# tea_maker_without_autorouter.net
KiCad netlist of a schematic drawn in EAGLE
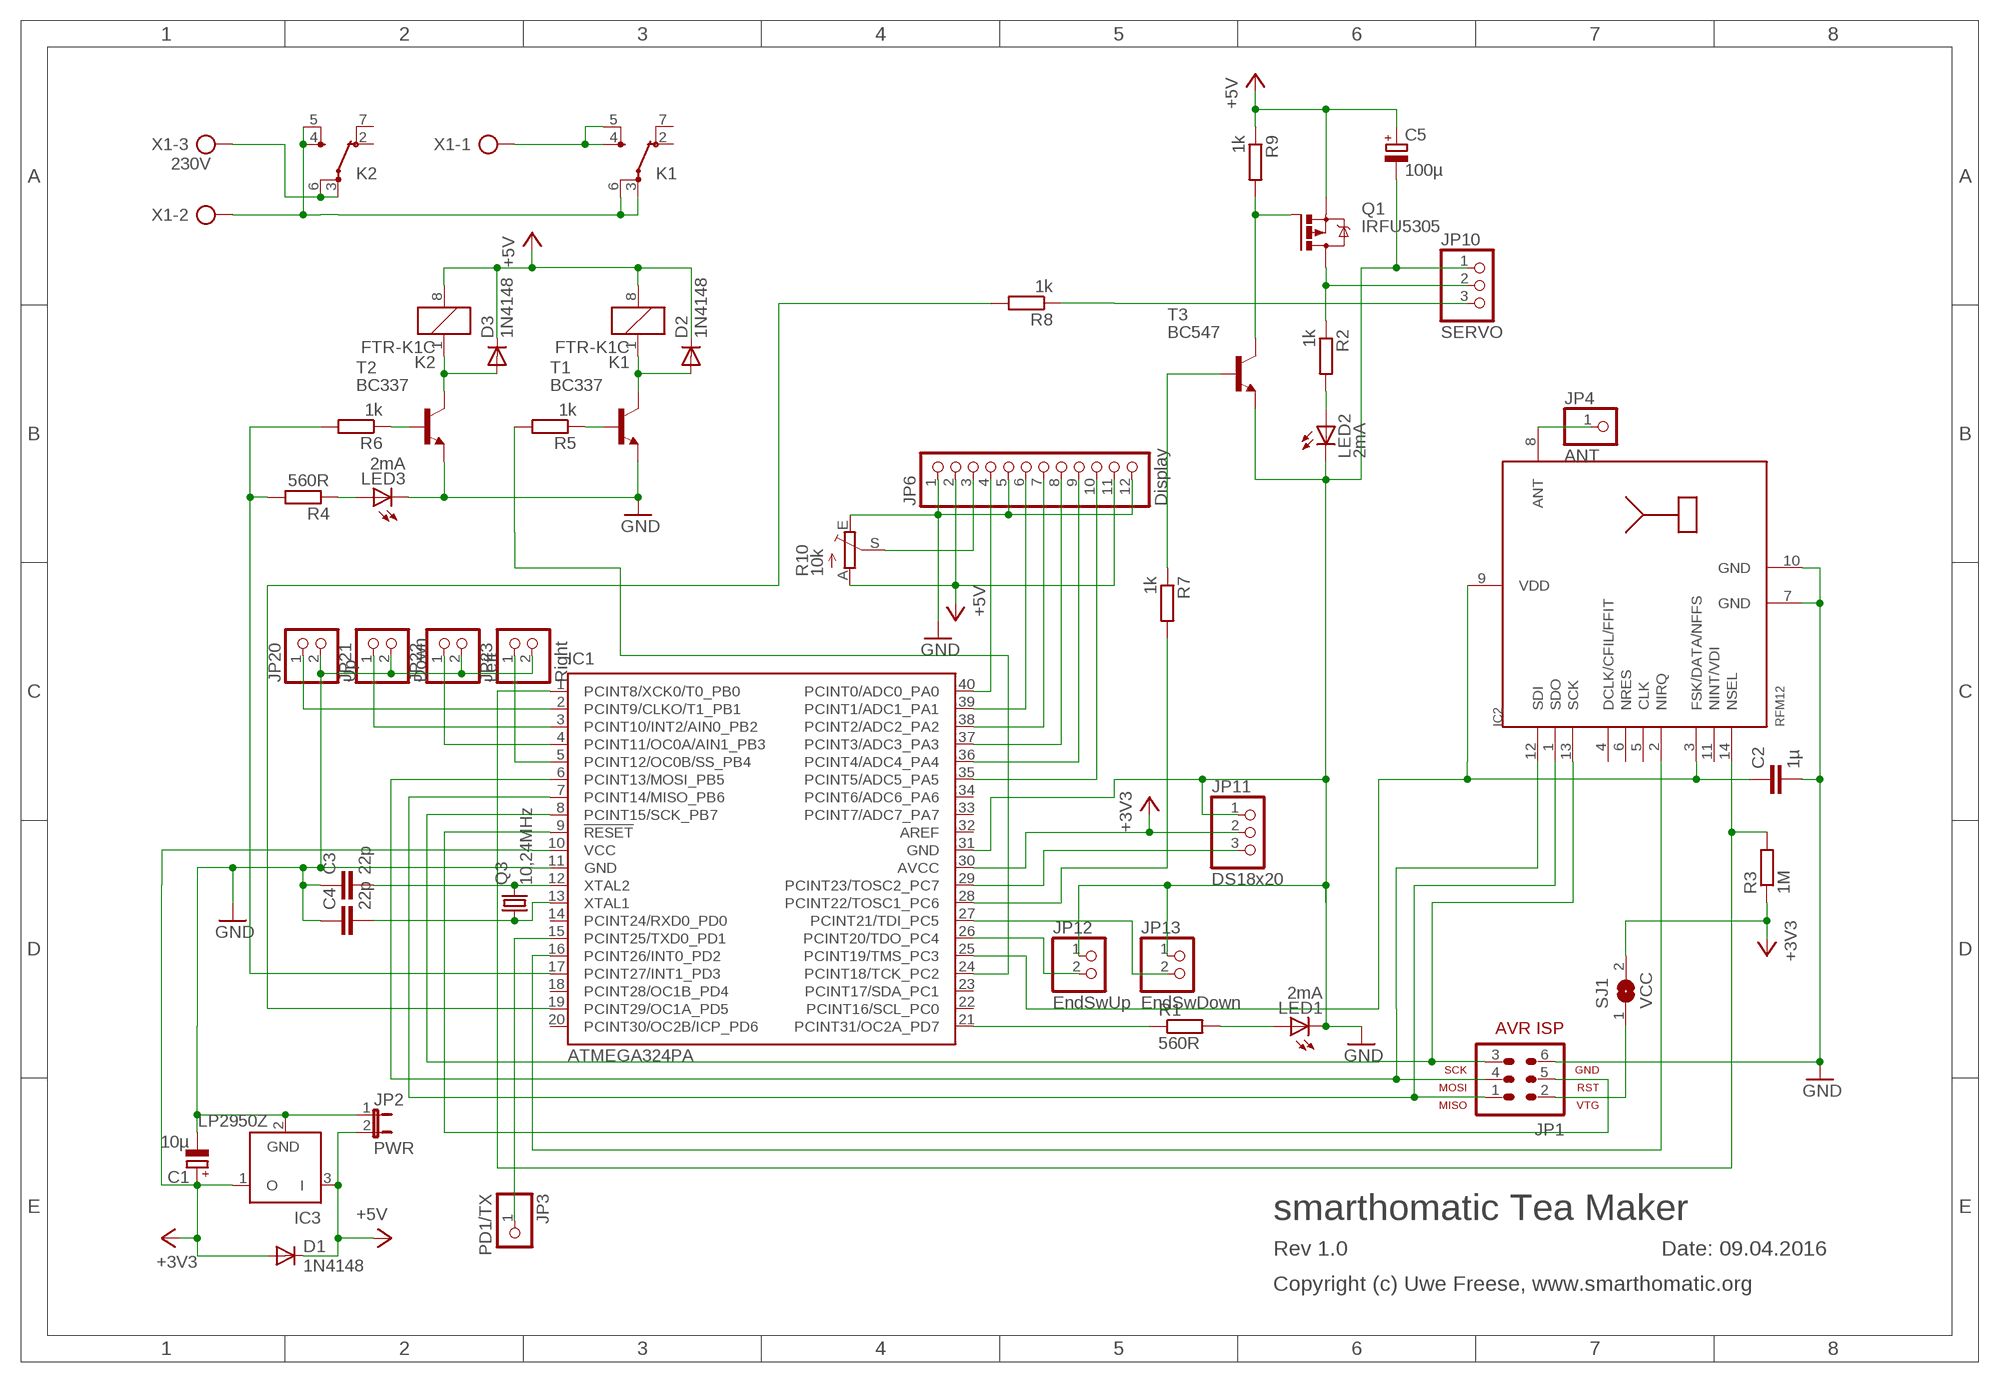
[diagram p0: schematic, sheet 1]

(export (version "E")
  (design (tool "Eeschema 10.0.6"))
  (components
    (comp (ref "C1")
      (value "10µ")
      (footprint "eagle-import:E1,8-4")
      (libsource (lib "eagle-import") (part "CPOL-EUE1.8-4"))
    )
    (comp (ref "C2")
      (value "1µ")
      (footprint "eagle-import:C5B3.5")
      (libsource (lib "eagle-import") (part "C5/3.5"))
    )
    (comp (ref "C3")
      (value "22p")
      (footprint "eagle-import:C025-024X044")
      (libsource (lib "eagle-import") (part "C-EU025-024X044"))
    )
    (comp (ref "C4")
      (value "22p")
      (footprint "eagle-import:C025-024X044")
      (libsource (lib "eagle-import") (part "C-EU025-024X044"))
    )
    (comp (ref "C5")
      (value "100µ")
      (footprint "eagle-import:E2,5-7")
      (libsource (lib "eagle-import") (part "CPOL-EUE2.5-7"))
    )
    (comp (ref "D1")
      (value "1N4148")
      (footprint "eagle-import:DO35-7")
      (libsource (lib "eagle-import") (part "1N4148DO35-7"))
    )
    (comp (ref "D2")
      (value "1N4148")
      (footprint "eagle-import:DO35-7")
      (libsource (lib "eagle-import") (part "1N4148DO35-7"))
    )
    (comp (ref "D3")
      (value "1N4148")
      (footprint "eagle-import:DO35-7")
      (libsource (lib "eagle-import") (part "1N4148DO35-7"))
    )
    (comp (ref "IC1")
      (value "ATMEGA324PA")
      (footprint "eagle-import:DIL40")
      (fields (field (name "MPN") "ATMEGA644V-10PU"))
      (libsource (lib "eagle-import") (part "ATMEGA644-PU10"))
    )
    (comp (ref "IC2")
      (value "RFM12")
      (footprint "eagle-import:RFM")
      (libsource (lib "eagle-import") (part "RFM12"))
    )
    (comp (ref "IC3")
      (value "LP2950Z")
      (footprint "eagle-import:TO92")
      (libsource (lib "eagle-import") (part "LP2950Z"))
    )
    (comp (ref "JP1")
      (value "AVR-ISP-6")
      (footprint "eagle-import:AVR-ISP-6")
      (libsource (lib "eagle-import") (part "AVR-ISP-6"))
    )
    (comp (ref "JP2")
      (value "PWR")
      (footprint "eagle-import:JP1")
      (libsource (lib "eagle-import") (part "JP1E"))
    )
    (comp (ref "JP3")
      (value "PD1/TX")
      (footprint "eagle-import:1X01")
      (libsource (lib "eagle-import") (part "PINHD-1X1"))
    )
    (comp (ref "JP4")
      (value "ANT")
      (footprint "eagle-import:1X01")
      (libsource (lib "eagle-import") (part "PINHD-1X1"))
    )
    (comp (ref "JP6")
      (value "Display")
      (footprint "eagle-import:1X12")
      (libsource (lib "eagle-import") (part "PINHD-1X12"))
    )
    (comp (ref "JP10")
      (value "SERVO")
      (footprint "eagle-import:1X03")
      (libsource (lib "eagle-import") (part "PINHD-1X3"))
    )
    (comp (ref "JP11")
      (value "DS18x20")
      (footprint "eagle-import:1X03")
      (libsource (lib "eagle-import") (part "PINHD-1X3"))
    )
    (comp (ref "JP12")
      (value "EndSwUp")
      (footprint "eagle-import:1X02")
      (libsource (lib "eagle-import") (part "PINHD-1X2"))
    )
    (comp (ref "JP13")
      (value "EndSwDown")
      (footprint "eagle-import:1X02")
      (libsource (lib "eagle-import") (part "PINHD-1X2"))
    )
    (comp (ref "JP20")
      (value "Up")
      (footprint "eagle-import:1X02")
      (libsource (lib "eagle-import") (part "PINHD-1X2"))
    )
    (comp (ref "JP21")
      (value "Down")
      (footprint "eagle-import:1X02")
      (libsource (lib "eagle-import") (part "PINHD-1X2"))
    )
    (comp (ref "JP22")
      (value "Left")
      (footprint "eagle-import:1X02")
      (libsource (lib "eagle-import") (part "PINHD-1X2"))
    )
    (comp (ref "JP23")
      (value "Right")
      (footprint "eagle-import:1X02")
      (libsource (lib "eagle-import") (part "PINHD-1X2"))
    )
    (comp (ref "K1")
      (value "FTR-K1C")
      (footprint "eagle-import:FTR-K1C")
      (libsource (lib "eagle-import") (part "FTR-K1C"))
    )
    (comp (ref "K2")
      (value "FTR-K1C")
      (footprint "eagle-import:FTR-K1C")
      (libsource (lib "eagle-import") (part "FTR-K1C"))
    )
    (comp (ref "LED1")
      (value "2mA")
      (footprint "eagle-import:LED3MM")
      (libsource (lib "eagle-import") (part "LED3MM"))
    )
    (comp (ref "LED2")
      (value "2mA")
      (footprint "eagle-import:LED3MM")
      (libsource (lib "eagle-import") (part "LED3MM"))
    )
    (comp (ref "LED3")
      (value "2mA")
      (footprint "eagle-import:LED3MM")
      (libsource (lib "eagle-import") (part "LED3MM"))
    )
    (comp (ref "Q1")
      (value "IRFU5305")
      (footprint "eagle-import:I-PAK_TO251AA")
      (libsource (lib "eagle-import") (part "IRF?5305U"))
    )
    (comp (ref "Q3")
      (value "10,24MHz")
      (footprint "eagle-import:HC49_S")
      (libsource (lib "eagle-import") (part "CRYSTALHC49S"))
    )
    (comp (ref "R1")
      (value "560R")
      (footprint "eagle-import:0207_7")
      (libsource (lib "eagle-import") (part "R-EU_0207/7"))
    )
    (comp (ref "R2")
      (value "1k")
      (footprint "eagle-import:0207_7")
      (libsource (lib "eagle-import") (part "R-EU_0207/7"))
    )
    (comp (ref "R3")
      (value "1M")
      (footprint "eagle-import:0207_7")
      (libsource (lib "eagle-import") (part "R-EU_0207/7"))
    )
    (comp (ref "R4")
      (value "560R")
      (footprint "eagle-import:0207_7")
      (libsource (lib "eagle-import") (part "R-EU_0207/7"))
    )
    (comp (ref "R5")
      (value "1k")
      (footprint "eagle-import:0207_7")
      (libsource (lib "eagle-import") (part "R-EU_0207/7"))
    )
    (comp (ref "R6")
      (value "1k")
      (footprint "eagle-import:0207_7")
      (libsource (lib "eagle-import") (part "R-EU_0207/7"))
    )
    (comp (ref "R7")
      (value "1k")
      (footprint "eagle-import:0207_7")
      (libsource (lib "eagle-import") (part "R-EU_0207/7"))
    )
    (comp (ref "R8")
      (value "1k")
      (footprint "eagle-import:0207_7")
      (libsource (lib "eagle-import") (part "R-EU_0207/7"))
    )
    (comp (ref "R9")
      (value "1k")
      (footprint "eagle-import:0207_7")
      (libsource (lib "eagle-import") (part "R-EU_0207/7"))
    )
    (comp (ref "R10")
      (value "10k")
      (footprint "eagle-import:PT-10S")
      (libsource (lib "eagle-import") (part "TRIM_EU-PT10S"))
    )
    (comp (ref "SJ1")
      (value "VCC")
      (footprint "eagle-import:SJ")
      (libsource (lib "eagle-import") (part "SJ"))
    )
    (comp (ref "T1")
      (value "BC337")
      (footprint "eagle-import:TO92")
      (libsource (lib "eagle-import") (part "BC337"))
    )
    (comp (ref "T2")
      (value "BC337")
      (footprint "eagle-import:TO92")
      (libsource (lib "eagle-import") (part "BC337"))
    )
    (comp (ref "T3")
      (value "BC547")
      (footprint "eagle-import:TO92")
      (libsource (lib "eagle-import") (part "BC547"))
    )
    (comp (ref "X1")
      (value "230V")
      (footprint "eagle-import:AK500_3")
      (libsource (lib "eagle-import") (part "AK500/3"))
    )
  )
  (nets
    (net (code "1") (name "+3V3") (class "Default")
      (node (ref "C1") (pin "+") (pinfunction "+_+") (pintype "passive"))
      (node (ref "D1") (pin "A") (pinfunction "A_A") (pintype "passive"))
      (node (ref "IC1") (pin "10") (pinfunction "VCC_10") (pintype "power_in"))
      (node (ref "IC1") (pin "30") (pinfunction "AVCC_30") (pintype "power_in"))
      (node (ref "IC3") (pin "1") (pinfunction "O_1") (pintype "input"))
      (node (ref "JP11") (pin "2") (pinfunction "2_2") (pintype "passive"))
      (node (ref "R3") (pin "1") (pinfunction "1_1") (pintype "passive"))
      (node (ref "SJ1") (pin "2") (pinfunction "2_2") (pintype "passive"))
    )
    (net (code "2") (name "+5V") (class "Default")
      (node (ref "C5") (pin "+") (pinfunction "+_+") (pintype "passive"))
      (node (ref "D1") (pin "C") (pinfunction "C_C") (pintype "passive"))
      (node (ref "D2") (pin "C") (pinfunction "C_C") (pintype "passive"))
      (node (ref "D3") (pin "C") (pinfunction "C_C") (pintype "passive"))
      (node (ref "IC3") (pin "3") (pinfunction "I_3") (pintype "input"))
      (node (ref "JP2") (pin "2") (pinfunction "2_2") (pintype "passive"))
      (node (ref "JP6") (pin "11") (pinfunction "11_11") (pintype "passive"))
      (node (ref "JP6") (pin "2") (pinfunction "2_2") (pintype "passive"))
      (node (ref "K1") (pin "8") (pinfunction "2_8") (pintype "passive"))
      (node (ref "K2") (pin "8") (pinfunction "2_8") (pintype "passive"))
      (node (ref "Q1") (pin "3") (pinfunction "S_3") (pintype "passive"))
      (node (ref "R10") (pin "A") (pinfunction "A_A") (pintype "passive"))
      (node (ref "R9") (pin "1") (pinfunction "1_1") (pintype "passive"))
    )
    (net (code "3") (name "GND") (class "Default")
      (node (ref "C1") (pin "-") (pinfunction "-_-") (pintype "passive"))
      (node (ref "C2") (pin "2") (pinfunction "2_2") (pintype "passive"))
      (node (ref "C3") (pin "1") (pinfunction "1_1") (pintype "passive"))
      (node (ref "C4") (pin "1") (pinfunction "1_1") (pintype "passive"))
      (node (ref "C5") (pin "-") (pinfunction "-_-") (pintype "passive"))
      (node (ref "IC1") (pin "11") (pinfunction "GND_11") (pintype "power_in"))
      (node (ref "IC1") (pin "31") (pinfunction "GND_31") (pintype "power_in"))
      (node (ref "IC2") (pin "10") (pinfunction "GND_10") (pintype "power_in"))
      (node (ref "IC2") (pin "7") (pinfunction "GND_7") (pintype "power_in"))
      (node (ref "IC3") (pin "2") (pinfunction "GND_2") (pintype "power_in"))
      (node (ref "JP1") (pin "6") (pinfunction "6_6") (pintype "passive"))
      (node (ref "JP10") (pin "1") (pinfunction "1_1") (pintype "passive"))
      (node (ref "JP11") (pin "1") (pinfunction "1_1") (pintype "passive"))
      (node (ref "JP12") (pin "1") (pinfunction "1_1") (pintype "passive"))
      (node (ref "JP13") (pin "1") (pinfunction "1_1") (pintype "passive"))
      (node (ref "JP2") (pin "1") (pinfunction "1_1") (pintype "passive"))
      (node (ref "JP20") (pin "2") (pinfunction "2_2") (pintype "passive"))
      (node (ref "JP21") (pin "2") (pinfunction "2_2") (pintype "passive"))
      (node (ref "JP22") (pin "2") (pinfunction "2_2") (pintype "passive"))
      (node (ref "JP23") (pin "2") (pinfunction "2_2") (pintype "passive"))
      (node (ref "JP6") (pin "1") (pinfunction "1_1") (pintype "passive"))
      (node (ref "JP6") (pin "12") (pinfunction "12_12") (pintype "passive"))
      (node (ref "JP6") (pin "5") (pinfunction "5_5") (pintype "passive"))
      (node (ref "LED1") (pin "K") (pinfunction "C_K") (pintype "passive"))
      (node (ref "LED2") (pin "K") (pinfunction "C_K") (pintype "passive"))
      (node (ref "LED3") (pin "K") (pinfunction "C_K") (pintype "passive"))
      (node (ref "R10") (pin "E") (pinfunction "E_E") (pintype "passive"))
      (node (ref "T1") (pin "1") (pinfunction "E_1") (pintype "passive"))
      (node (ref "T2") (pin "1") (pinfunction "E_1") (pintype "passive"))
      (node (ref "T3") (pin "1") (pinfunction "E_1") (pintype "passive"))
    )
    (net (code "4") (name "Net-(IC1-PCINT0{slash}ADC0_PA0)") (class "Default")
      (node (ref "IC1") (pin "40") (pinfunction "PCINT0/ADC0_PA0_40") (pintype "bidirectional"))
      (node (ref "JP6") (pin "4") (pinfunction "4_4") (pintype "passive"))
    )
    (net (code "5") (name "Net-(IC1-PCINT1{slash}ADC1_PA1)") (class "Default")
      (node (ref "IC1") (pin "39") (pinfunction "PCINT1/ADC1_PA1_39") (pintype "bidirectional"))
      (node (ref "JP6") (pin "6") (pinfunction "6_6") (pintype "passive"))
    )
    (net (code "6") (name "Net-(IC1-PCINT2{slash}ADC2_PA2)") (class "Default")
      (node (ref "IC1") (pin "38") (pinfunction "PCINT2/ADC2_PA2_38") (pintype "bidirectional"))
      (node (ref "JP6") (pin "7") (pinfunction "7_7") (pintype "passive"))
    )
    (net (code "7") (name "Net-(IC1-PCINT3{slash}ADC3_PA3)") (class "Default")
      (node (ref "IC1") (pin "37") (pinfunction "PCINT3/ADC3_PA3_37") (pintype "bidirectional"))
      (node (ref "JP6") (pin "8") (pinfunction "8_8") (pintype "passive"))
    )
    (net (code "8") (name "Net-(IC1-PCINT4{slash}ADC4_PA4)") (class "Default")
      (node (ref "IC1") (pin "36") (pinfunction "PCINT4/ADC4_PA4_36") (pintype "bidirectional"))
      (node (ref "JP6") (pin "9") (pinfunction "9_9") (pintype "passive"))
    )
    (net (code "9") (name "Net-(IC1-PCINT5{slash}ADC5_PA5)") (class "Default")
      (node (ref "IC1") (pin "35") (pinfunction "PCINT5/ADC5_PA5_35") (pintype "bidirectional"))
      (node (ref "JP6") (pin "10") (pinfunction "10_10") (pintype "passive"))
    )
    (net (code "10") (name "Net-(IC1-PCINT8{slash}XCK0{slash}T0_PB0)") (class "Default")
      (node (ref "IC1") (pin "1") (pinfunction "PCINT8/XCK0/T0_PB0_1") (pintype "bidirectional"))
      (node (ref "IC2") (pin "14") (pinfunction "NSEL_14") (pintype "bidirectional"))
      (node (ref "R3") (pin "2") (pinfunction "2_2") (pintype "passive"))
    )
    (net (code "11") (name "Net-(IC1-PCINT9{slash}CLKO{slash}T1_PB1)") (class "Default")
      (node (ref "IC1") (pin "2") (pinfunction "PCINT9/CLKO/T1_PB1_2") (pintype "bidirectional"))
      (node (ref "JP20") (pin "1") (pinfunction "1_1") (pintype "passive"))
    )
    (net (code "12") (name "Net-(IC1-PCINT10{slash}INT2{slash}AIN0_PB2)") (class "Default")
      (node (ref "IC1") (pin "3") (pinfunction "PCINT10/INT2/AIN0_PB2_3") (pintype "bidirectional"))
      (node (ref "JP21") (pin "1") (pinfunction "1_1") (pintype "passive"))
    )
    (net (code "13") (name "Net-(IC1-PCINT11{slash}OC0A{slash}AIN1_PB3)") (class "Default")
      (node (ref "IC1") (pin "4") (pinfunction "PCINT11/OC0A/AIN1_PB3_4") (pintype "bidirectional"))
      (node (ref "JP22") (pin "1") (pinfunction "1_1") (pintype "passive"))
    )
    (net (code "14") (name "Net-(IC1-PCINT12{slash}OC0B{slash}SS_PB4)") (class "Default")
      (node (ref "IC1") (pin "5") (pinfunction "PCINT12/OC0B/SS_PB4_5") (pintype "bidirectional"))
      (node (ref "JP23") (pin "1") (pinfunction "1_1") (pintype "passive"))
    )
    (net (code "15") (name "Net-(IC1-PCINT13{slash}MOSI_PB5)") (class "Default")
      (node (ref "IC1") (pin "6") (pinfunction "PCINT13/MOSI_PB5_6") (pintype "bidirectional"))
      (node (ref "IC2") (pin "12") (pinfunction "SDI_12") (pintype "bidirectional"))
      (node (ref "JP1") (pin "4") (pinfunction "4_4") (pintype "passive"))
    )
    (net (code "16") (name "Net-(IC1-PCINT14{slash}MISO_PB6)") (class "Default")
      (node (ref "IC1") (pin "7") (pinfunction "PCINT14/MISO_PB6_7") (pintype "bidirectional"))
      (node (ref "IC2") (pin "1") (pinfunction "SDO_1") (pintype "bidirectional"))
      (node (ref "JP1") (pin "1") (pinfunction "1_1") (pintype "passive"))
    )
    (net (code "17") (name "Net-(IC1-PCINT15{slash}SCK_PB7)") (class "Default")
      (node (ref "IC1") (pin "8") (pinfunction "PCINT15/SCK_PB7_8") (pintype "bidirectional"))
      (node (ref "IC2") (pin "13") (pinfunction "SCK_13") (pintype "bidirectional"))
      (node (ref "JP1") (pin "3") (pinfunction "3_3") (pintype "passive"))
    )
    (net (code "18") (name "Net-(IC1-PCINT18{slash}TCK_PC2)") (class "Default")
      (node (ref "IC1") (pin "24") (pinfunction "PCINT18/TCK_PC2_24") (pintype "bidirectional"))
      (node (ref "R5") (pin "2") (pinfunction "2_2") (pintype "passive"))
    )
    (net (code "19") (name "Net-(IC1-PCINT19{slash}TMS_PC3)") (class "Default")
      (node (ref "C2") (pin "1") (pinfunction "1_1") (pintype "passive"))
      (node (ref "IC1") (pin "25") (pinfunction "PCINT19/TMS_PC3_25") (pintype "bidirectional"))
      (node (ref "IC2") (pin "3") (pinfunction "FSK/DATA/NFFS_3") (pintype "bidirectional"))
      (node (ref "IC2") (pin "9") (pinfunction "VDD_9") (pintype "power_in"))
    )
    (net (code "20") (name "Net-(IC1-PCINT20{slash}TDO_PC4)") (class "Default")
      (node (ref "IC1") (pin "26") (pinfunction "PCINT20/TDO_PC4_26") (pintype "bidirectional"))
      (node (ref "JP12") (pin "2") (pinfunction "2_2") (pintype "passive"))
    )
    (net (code "21") (name "Net-(IC1-PCINT21{slash}TDI_PC5)") (class "Default")
      (node (ref "IC1") (pin "27") (pinfunction "PCINT21/TDI_PC5_27") (pintype "bidirectional"))
      (node (ref "JP13") (pin "2") (pinfunction "2_2") (pintype "passive"))
    )
    (net (code "22") (name "Net-(IC1-PCINT22{slash}TOSC1_PC6)") (class "Default")
      (node (ref "IC1") (pin "28") (pinfunction "PCINT22/TOSC1_PC6_28") (pintype "bidirectional"))
      (node (ref "R7") (pin "2") (pinfunction "2_2") (pintype "passive"))
    )
    (net (code "23") (name "Net-(IC1-PCINT23{slash}TOSC2_PC7)") (class "Default")
      (node (ref "IC1") (pin "29") (pinfunction "PCINT23/TOSC2_PC7_29") (pintype "bidirectional"))
      (node (ref "JP11") (pin "3") (pinfunction "3_3") (pintype "passive"))
    )
    (net (code "24") (name "Net-(IC1-PCINT25{slash}TXD0_PD1)") (class "Default")
      (node (ref "IC1") (pin "15") (pinfunction "PCINT25/TXD0_PD1_15") (pintype "bidirectional"))
      (node (ref "JP3") (pin "1") (pinfunction "1_1") (pintype "passive"))
    )
    (net (code "25") (name "Net-(IC1-PCINT26{slash}INT0_PD2)") (class "Default")
      (node (ref "IC1") (pin "16") (pinfunction "PCINT26/INT0_PD2_16") (pintype "bidirectional"))
      (node (ref "IC2") (pin "2") (pinfunction "NIRQ_2") (pintype "bidirectional"))
    )
    (net (code "26") (name "Net-(IC1-PCINT27{slash}INT1_PD3)") (class "Default")
      (node (ref "IC1") (pin "17") (pinfunction "PCINT27/INT1_PD3_17") (pintype "bidirectional"))
      (node (ref "R4") (pin "2") (pinfunction "2_2") (pintype "passive"))
      (node (ref "R6") (pin "2") (pinfunction "2_2") (pintype "passive"))
    )
    (net (code "27") (name "Net-(IC1-PCINT29{slash}OC1A_PD5)") (class "Default")
      (node (ref "IC1") (pin "19") (pinfunction "PCINT29/OC1A_PD5_19") (pintype "bidirectional"))
      (node (ref "R8") (pin "2") (pinfunction "2_2") (pintype "passive"))
    )
    (net (code "28") (name "Net-(IC1-PCINT31{slash}OC2A_PD7)") (class "Default")
      (node (ref "IC1") (pin "21") (pinfunction "PCINT31/OC2A_PD7_21") (pintype "bidirectional"))
      (node (ref "R1") (pin "1") (pinfunction "1_1") (pintype "passive"))
    )
    (net (code "29") (name "Net-(IC1-XTAL1)") (class "Default")
      (node (ref "C4") (pin "2") (pinfunction "2_2") (pintype "passive"))
      (node (ref "IC1") (pin "13") (pinfunction "XTAL1_13") (pintype "input"))
      (node (ref "Q3") (pin "1") (pinfunction "1_1") (pintype "passive"))
    )
    (net (code "30") (name "Net-(IC1-XTAL2)") (class "Default")
      (node (ref "C3") (pin "2") (pinfunction "2_2") (pintype "passive"))
      (node (ref "IC1") (pin "12") (pinfunction "XTAL2_12") (pintype "output"))
      (node (ref "Q3") (pin "2") (pinfunction "2_2") (pintype "passive"))
    )
    (net (code "31") (name "Net-(IC1-~{RESET})") (class "Default")
      (node (ref "IC1") (pin "9") (pinfunction "~{RESET}_9") (pintype "input"))
      (node (ref "JP1") (pin "5") (pinfunction "5_5") (pintype "passive"))
    )
    (net (code "32") (name "Net-(IC2-ANT)") (class "Default")
      (node (ref "IC2") (pin "8") (pinfunction "ANT_8") (pintype "output"))
      (node (ref "JP4") (pin "1") (pinfunction "1_1") (pintype "passive"))
    )
    (net (code "33") (name "Net-(JP1-Pad2)") (class "Default")
      (node (ref "JP1") (pin "2") (pinfunction "2_2") (pintype "passive"))
      (node (ref "SJ1") (pin "1") (pinfunction "1_1") (pintype "passive"))
    )
    (net (code "34") (name "Net-(JP6-Pad3)") (class "Default")
      (node (ref "JP6") (pin "3") (pinfunction "3_3") (pintype "passive"))
      (node (ref "R10") (pin "S") (pinfunction "S_S") (pintype "passive"))
    )
    (net (code "35") (name "Net-(JP10-Pad3)") (class "Default")
      (node (ref "JP10") (pin "3") (pinfunction "3_3") (pintype "passive"))
      (node (ref "R8") (pin "1") (pinfunction "1_1") (pintype "passive"))
    )
    (net (code "36") (name "Net-(K1A-PA)") (class "Default")
      (node (ref "K1") (pin "3") (pinfunction "PA_3") (pintype "passive"))
      (node (ref "K1") (pin "6") (pinfunction "PB_6") (pintype "passive"))
      (node (ref "K2") (pin "4") (pinfunction "SA_4") (pintype "passive"))
      (node (ref "K2") (pin "5") (pinfunction "SB_5") (pintype "passive"))
      (node (ref "X1") (pin "2") (pinfunction "KL_2") (pintype "passive"))
    )
    (net (code "37") (name "Net-(K1A-SA)") (class "Default")
      (node (ref "K1") (pin "4") (pinfunction "SA_4") (pintype "passive"))
      (node (ref "K1") (pin "5") (pinfunction "SB_5") (pintype "passive"))
      (node (ref "X1") (pin "1") (pinfunction "KL_1") (pintype "passive"))
    )
    (net (code "38") (name "Net-(K2A-PA)") (class "Default")
      (node (ref "K2") (pin "3") (pinfunction "PA_3") (pintype "passive"))
      (node (ref "K2") (pin "6") (pinfunction "PB_6") (pintype "passive"))
      (node (ref "X1") (pin "3") (pinfunction "KL_3") (pintype "passive"))
    )
    (net (code "39") (name "Net-(LED1-PadA)") (class "Default")
      (node (ref "LED1") (pin "A") (pinfunction "A_A") (pintype "passive"))
      (node (ref "R1") (pin "2") (pinfunction "2_2") (pintype "passive"))
    )
    (net (code "40") (name "Net-(LED2-PadA)") (class "Default")
      (node (ref "LED2") (pin "A") (pinfunction "A_A") (pintype "passive"))
      (node (ref "R2") (pin "2") (pinfunction "2_2") (pintype "passive"))
    )
    (net (code "41") (name "Net-(LED3-PadA)") (class "Default")
      (node (ref "LED3") (pin "A") (pinfunction "A_A") (pintype "passive"))
      (node (ref "R4") (pin "1") (pinfunction "1_1") (pintype "passive"))
    )
    (net (code "42") (name "Net-(Q1-D)") (class "Default")
      (node (ref "JP10") (pin "2") (pinfunction "2_2") (pintype "passive"))
      (node (ref "Q1") (pin "2") (pinfunction "D_2") (pintype "passive"))
      (node (ref "R2") (pin "1") (pinfunction "1_1") (pintype "passive"))
    )
    (net (code "43") (name "Net-(Q1-G)") (class "Default")
      (node (ref "Q1") (pin "1") (pinfunction "G_1") (pintype "passive"))
      (node (ref "R9") (pin "2") (pinfunction "2_2") (pintype "passive"))
      (node (ref "T3") (pin "3") (pinfunction "C_3") (pintype "passive"))
    )
    (net (code "44") (name "Net-(T1-B)") (class "Default")
      (node (ref "R5") (pin "1") (pinfunction "1_1") (pintype "passive"))
      (node (ref "T1") (pin "2") (pinfunction "B_2") (pintype "passive"))
    )
    (net (code "45") (name "Net-(T1-C)") (class "Default")
      (node (ref "D2") (pin "A") (pinfunction "A_A") (pintype "passive"))
      (node (ref "K1") (pin "1") (pinfunction "1_1") (pintype "passive"))
      (node (ref "T1") (pin "3") (pinfunction "C_3") (pintype "passive"))
    )
    (net (code "46") (name "Net-(T2-B)") (class "Default")
      (node (ref "R6") (pin "1") (pinfunction "1_1") (pintype "passive"))
      (node (ref "T2") (pin "2") (pinfunction "B_2") (pintype "passive"))
    )
    (net (code "47") (name "Net-(T2-C)") (class "Default")
      (node (ref "D3") (pin "A") (pinfunction "A_A") (pintype "passive"))
      (node (ref "K2") (pin "1") (pinfunction "1_1") (pintype "passive"))
      (node (ref "T2") (pin "3") (pinfunction "C_3") (pintype "passive"))
    )
    (net (code "48") (name "Net-(T3-B)") (class "Default")
      (node (ref "R7") (pin "1") (pinfunction "1_1") (pintype "passive"))
      (node (ref "T3") (pin "2") (pinfunction "B_2") (pintype "passive"))
    )
    (net (code "49") (name "unconnected-(IC1-AREF-Pad32)") (class "Default")
      (node (ref "IC1") (pin "32") (pinfunction "AREF_32") (pintype "passive"))
    )
    (net (code "50") (name "unconnected-(IC1-PCINT6{slash}ADC6_PA6-Pad34)") (class "Default")
      (node (ref "IC1") (pin "34") (pinfunction "PCINT6/ADC6_PA6_34") (pintype "bidirectional"))
    )
    (net (code "51") (name "unconnected-(IC1-PCINT7{slash}ADC7_PA7-Pad33)") (class "Default")
      (node (ref "IC1") (pin "33") (pinfunction "PCINT7/ADC7_PA7_33") (pintype "bidirectional"))
    )
    (net (code "52") (name "unconnected-(IC1-PCINT16{slash}SCL_PC0-Pad22)") (class "Default")
      (node (ref "IC1") (pin "22") (pinfunction "PCINT16/SCL_PC0_22") (pintype "bidirectional"))
    )
    (net (code "53") (name "unconnected-(IC1-PCINT17{slash}SDA_PC1-Pad23)") (class "Default")
      (node (ref "IC1") (pin "23") (pinfunction "PCINT17/SDA_PC1_23") (pintype "bidirectional"))
    )
    (net (code "54") (name "unconnected-(IC1-PCINT24{slash}RXD0_PD0-Pad14)") (class "Default")
      (node (ref "IC1") (pin "14") (pinfunction "PCINT24/RXD0_PD0_14") (pintype "bidirectional"))
    )
    (net (code "55") (name "unconnected-(IC1-PCINT28{slash}OC1B_PD4-Pad18)") (class "Default")
      (node (ref "IC1") (pin "18") (pinfunction "PCINT28/OC1B_PD4_18") (pintype "bidirectional"))
    )
    (net (code "56") (name "unconnected-(IC1-PCINT30{slash}OC2B{slash}ICP_PD6-Pad20)") (class "Default")
      (node (ref "IC1") (pin "20") (pinfunction "PCINT30/OC2B/ICP_PD6_20") (pintype "bidirectional"))
    )
    (net (code "57") (name "unconnected-(IC2-CLK-Pad5)") (class "Default")
      (node (ref "IC2") (pin "5") (pinfunction "CLK_5") (pintype "bidirectional"))
    )
    (net (code "58") (name "unconnected-(IC2-DCLK{slash}CFIL{slash}FFIT-Pad4)") (class "Default")
      (node (ref "IC2") (pin "4") (pinfunction "DCLK/CFIL/FFIT_4") (pintype "bidirectional"))
    )
    (net (code "59") (name "unconnected-(IC2-NINT{slash}VDI-Pad11)") (class "Default")
      (node (ref "IC2") (pin "11") (pinfunction "NINT/VDI_11") (pintype "bidirectional"))
    )
    (net (code "60") (name "unconnected-(IC2-NRES-Pad6)") (class "Default")
      (node (ref "IC2") (pin "6") (pinfunction "NRES_6") (pintype "bidirectional"))
    )
    (net (code "61") (name "unconnected-(K1A-OA-Pad2)") (class "Default")
      (node (ref "K1") (pin "2") (pinfunction "OA_2") (pintype "passive"))
    )
    (net (code "62") (name "unconnected-(K1A-OB-Pad7)") (class "Default")
      (node (ref "K1") (pin "7") (pinfunction "OB_7") (pintype "passive"))
    )
    (net (code "63") (name "unconnected-(K2A-OA-Pad2)") (class "Default")
      (node (ref "K2") (pin "2") (pinfunction "OA_2") (pintype "passive"))
    )
    (net (code "64") (name "unconnected-(K2A-OB-Pad7)") (class "Default")
      (node (ref "K2") (pin "7") (pinfunction "OB_7") (pintype "passive"))
    )
  )
)
